# Sheet1.net
KiCad netlist of a schematic drawn in Altium Designer
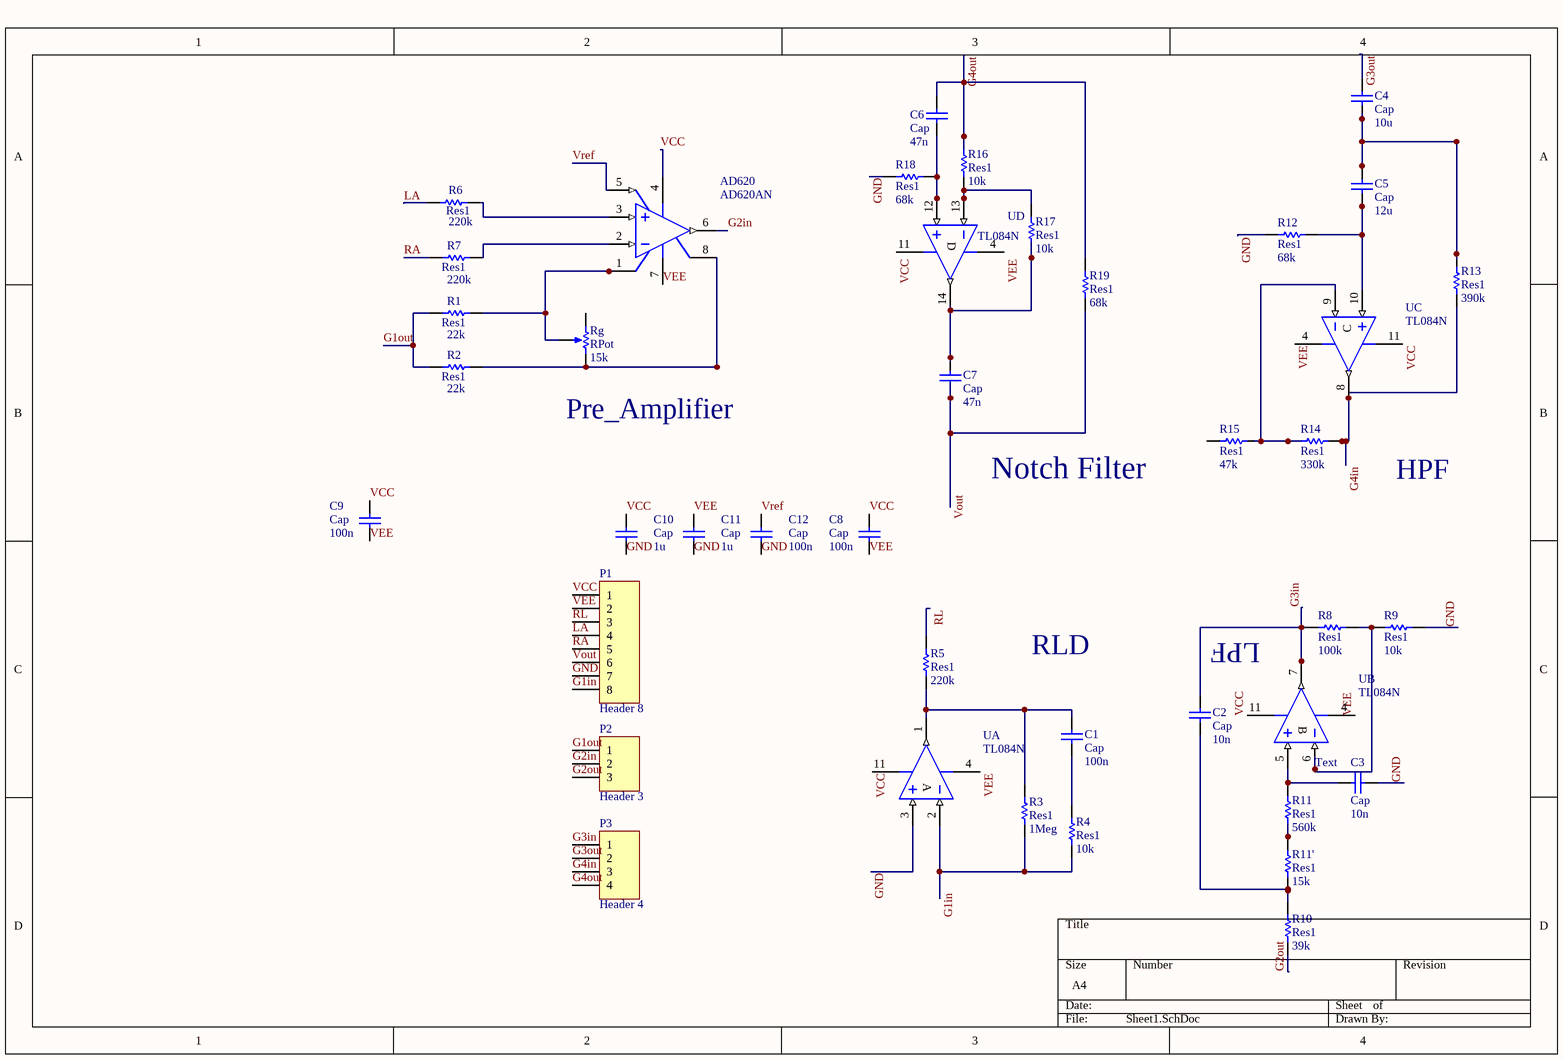
[diagram p0: Sheet1.SchDoc]

(export (version "E")
  (design (tool "Eeschema 10.0.6"))
  (components
    (comp (ref "AD620")
      (value "AD620AN")
      (footprint "N-8")
      (description "Low-Cost, Low-Power Instrumentation Amplifier")
      (fields (field (name "PUBLISHER") "Altium Limited"))
      (libsource (lib "AD Instrumentation Amplifier") (part "AD620AN"))
    )
    (comp (ref "C1")
      (value "Cap")
      (footprint "RAD-0.3")
      (description "Capacitor")
      (fields (field (name "ALTIUM_VALUE") "100n") (field (name "PUBLISHER") "Altium Limited"))
      (libsource (lib "Miscellaneous Devices") (part "Cap"))
    )
    (comp (ref "C2")
      (value "Cap")
      (footprint "RAD-0.3")
      (description "Capacitor")
      (fields (field (name "ALTIUM_VALUE") "10n") (field (name "PUBLISHER") "Altium Limited"))
      (libsource (lib "Miscellaneous Devices") (part "Cap"))
    )
    (comp (ref "C3")
      (value "Cap")
      (footprint "RAD-0.3")
      (description "Capacitor")
      (fields (field (name "ALTIUM_VALUE") "10n") (field (name "PUBLISHER") "Altium Limited"))
      (libsource (lib "Miscellaneous Devices") (part "Cap"))
    )
    (comp (ref "C4")
      (value "Cap")
      (footprint "RAD-0.3")
      (description "Capacitor")
      (fields (field (name "ALTIUM_VALUE") "10u") (field (name "PUBLISHER") "Altium Limited"))
      (libsource (lib "Miscellaneous Devices") (part "Cap"))
    )
    (comp (ref "C5")
      (value "Cap")
      (footprint "RAD-0.3")
      (description "Capacitor")
      (fields (field (name "ALTIUM_VALUE") "12u") (field (name "PUBLISHER") "Altium Limited"))
      (libsource (lib "Miscellaneous Devices") (part "Cap"))
    )
    (comp (ref "C6")
      (value "Cap")
      (footprint "RAD-0.3")
      (description "Capacitor")
      (fields (field (name "ALTIUM_VALUE") "47n") (field (name "PUBLISHER") "Altium Limited"))
      (libsource (lib "Miscellaneous Devices") (part "Cap"))
    )
    (comp (ref "C7")
      (value "Cap")
      (footprint "RAD-0.3")
      (description "Capacitor")
      (fields (field (name "ALTIUM_VALUE") "47n") (field (name "PUBLISHER") "Altium Limited"))
      (libsource (lib "Miscellaneous Devices") (part "Cap"))
    )
    (comp (ref "C8")
      (value "Cap")
      (footprint "RAD-0.3")
      (description "Capacitor")
      (fields (field (name "ALTIUM_VALUE") "100n") (field (name "PUBLISHER") "Altium Limited"))
      (libsource (lib "Miscellaneous Devices") (part "Cap"))
    )
    (comp (ref "C9")
      (value "Cap")
      (footprint "RAD-0.3")
      (description "Capacitor")
      (fields (field (name "ALTIUM_VALUE") "100n") (field (name "PUBLISHER") "Altium Limited"))
      (libsource (lib "Miscellaneous Devices") (part "Cap"))
    )
    (comp (ref "C10")
      (value "Cap")
      (footprint "RAD-0.3")
      (description "Capacitor")
      (fields (field (name "ALTIUM_VALUE") "1u") (field (name "PUBLISHER") "Altium Limited"))
      (libsource (lib "Miscellaneous Devices") (part "Cap"))
    )
    (comp (ref "C11")
      (value "Cap")
      (footprint "RAD-0.3")
      (description "Capacitor")
      (fields (field (name "ALTIUM_VALUE") "1u") (field (name "PUBLISHER") "Altium Limited"))
      (libsource (lib "Miscellaneous Devices") (part "Cap"))
    )
    (comp (ref "C12")
      (value "Cap")
      (footprint "RAD-0.3")
      (description "Capacitor")
      (fields (field (name "ALTIUM_VALUE") "100n") (field (name "PUBLISHER") "Altium Limited"))
      (libsource (lib "Miscellaneous Devices") (part "Cap"))
    )
    (comp (ref "P1")
      (value "Header 8")
      (footprint "HDR1X8")
      (description "Header, 8-Pin")
      (fields (field (name "PUBLISHER") "Altium Limited"))
      (libsource (lib "Miscellaneous Connectors") (part "Header 8"))
    )
    (comp (ref "P2")
      (value "Header 3")
      (footprint "HDR1X3")
      (description "Header, 3-Pin")
      (fields (field (name "PUBLISHER") "Altium Limited"))
      (libsource (lib "Miscellaneous Connectors") (part "Header 3"))
    )
    (comp (ref "P3")
      (value "Header 4")
      (footprint "HDR1X4")
      (description "Header, 4-Pin")
      (fields (field (name "PUBLISHER") "Altium Limited"))
      (libsource (lib "Miscellaneous Connectors") (part "Header 4"))
    )
    (comp (ref "R1")
      (value "Res1")
      (footprint "AXIAL-0.3")
      (description "Resistor")
      (fields (field (name "ALTIUM_VALUE") "22k") (field (name "PUBLISHER") "Altium Limited"))
      (libsource (lib "Miscellaneous Devices") (part "Res1"))
    )
    (comp (ref "R2")
      (value "Res1")
      (footprint "AXIAL-0.3")
      (description "Resistor")
      (fields (field (name "ALTIUM_VALUE") "22k") (field (name "PUBLISHER") "Altium Limited"))
      (libsource (lib "Miscellaneous Devices") (part "Res1"))
    )
    (comp (ref "R3")
      (value "Res1")
      (footprint "AXIAL-0.3")
      (description "Resistor")
      (fields (field (name "ALTIUM_VALUE") "1Meg") (field (name "PUBLISHER") "Altium Limited"))
      (libsource (lib "Miscellaneous Devices") (part "Res1"))
    )
    (comp (ref "R4")
      (value "Res1")
      (footprint "AXIAL-0.3")
      (description "Resistor")
      (fields (field (name "ALTIUM_VALUE") "10k") (field (name "PUBLISHER") "Altium Limited"))
      (libsource (lib "Miscellaneous Devices") (part "Res1"))
    )
    (comp (ref "R5")
      (value "Res1")
      (footprint "AXIAL-0.3")
      (description "Resistor")
      (fields (field (name "ALTIUM_VALUE") "220k") (field (name "PUBLISHER") "Altium Limited"))
      (libsource (lib "Miscellaneous Devices") (part "Res1"))
    )
    (comp (ref "R6")
      (value "Res1")
      (footprint "AXIAL-0.3")
      (description "Resistor")
      (fields (field (name "ALTIUM_VALUE") "220k") (field (name "PUBLISHER") "Altium Limited"))
      (libsource (lib "Miscellaneous Devices") (part "Res1"))
    )
    (comp (ref "R7")
      (value "Res1")
      (footprint "AXIAL-0.3")
      (description "Resistor")
      (fields (field (name "ALTIUM_VALUE") "220k") (field (name "PUBLISHER") "Altium Limited"))
      (libsource (lib "Miscellaneous Devices") (part "Res1"))
    )
    (comp (ref "R8")
      (value "Res1")
      (footprint "AXIAL-0.3")
      (description "Resistor")
      (fields (field (name "ALTIUM_VALUE") "100k") (field (name "PUBLISHER") "Altium Limited"))
      (libsource (lib "Miscellaneous Devices") (part "Res1"))
    )
    (comp (ref "R9")
      (value "Res1")
      (footprint "AXIAL-0.3")
      (description "Resistor")
      (fields (field (name "ALTIUM_VALUE") "10k") (field (name "PUBLISHER") "Altium Limited"))
      (libsource (lib "Miscellaneous Devices") (part "Res1"))
    )
    (comp (ref "R10")
      (value "Res1")
      (footprint "AXIAL-0.3")
      (description "Resistor")
      (fields (field (name "ALTIUM_VALUE") "39k") (field (name "PUBLISHER") "Altium Limited"))
      (libsource (lib "Miscellaneous Devices") (part "Res1"))
    )
    (comp (ref "R11")
      (value "Res1")
      (footprint "AXIAL-0.3")
      (description "Resistor")
      (fields (field (name "ALTIUM_VALUE") "560k") (field (name "PUBLISHER") "Altium Limited"))
      (libsource (lib "Miscellaneous Devices") (part "Res1"))
    )
    (comp (ref "R11'")
      (value "Res1")
      (footprint "AXIAL-0.3")
      (description "Resistor")
      (fields (field (name "ALTIUM_VALUE") "15k") (field (name "PUBLISHER") "Altium Limited"))
      (libsource (lib "Miscellaneous Devices") (part "Res1"))
    )
    (comp (ref "R12")
      (value "Res1")
      (footprint "AXIAL-0.3")
      (description "Resistor")
      (fields (field (name "ALTIUM_VALUE") "68k") (field (name "PUBLISHER") "Altium Limited"))
      (libsource (lib "Miscellaneous Devices") (part "Res1"))
    )
    (comp (ref "R13")
      (value "Res1")
      (footprint "AXIAL-0.3")
      (description "Resistor")
      (fields (field (name "ALTIUM_VALUE") "390k") (field (name "PUBLISHER") "Altium Limited"))
      (libsource (lib "Miscellaneous Devices") (part "Res1"))
    )
    (comp (ref "R14")
      (value "Res1")
      (footprint "AXIAL-0.3")
      (description "Resistor")
      (fields (field (name "ALTIUM_VALUE") "330k") (field (name "PUBLISHER") "Altium Limited"))
      (libsource (lib "Miscellaneous Devices") (part "Res1"))
    )
    (comp (ref "R15")
      (value "Res1")
      (footprint "AXIAL-0.3")
      (description "Resistor")
      (fields (field (name "ALTIUM_VALUE") "47k") (field (name "PUBLISHER") "Altium Limited"))
      (libsource (lib "Miscellaneous Devices") (part "Res1"))
    )
    (comp (ref "R16")
      (value "Res1")
      (footprint "AXIAL-0.3")
      (description "Resistor")
      (fields (field (name "ALTIUM_VALUE") "10k") (field (name "PUBLISHER") "Altium Limited"))
      (libsource (lib "Miscellaneous Devices") (part "Res1"))
    )
    (comp (ref "R17")
      (value "Res1")
      (footprint "AXIAL-0.3")
      (description "Resistor")
      (fields (field (name "ALTIUM_VALUE") "10k") (field (name "PUBLISHER") "Altium Limited"))
      (libsource (lib "Miscellaneous Devices") (part "Res1"))
    )
    (comp (ref "R18")
      (value "Res1")
      (footprint "AXIAL-0.3")
      (description "Resistor")
      (fields (field (name "ALTIUM_VALUE") "68k") (field (name "PUBLISHER") "Altium Limited"))
      (libsource (lib "Miscellaneous Devices") (part "Res1"))
    )
    (comp (ref "R19")
      (value "Res1")
      (footprint "AXIAL-0.3")
      (description "Resistor")
      (fields (field (name "ALTIUM_VALUE") "68k") (field (name "PUBLISHER") "Altium Limited"))
      (libsource (lib "Miscellaneous Devices") (part "Res1"))
    )
    (comp (ref "Rg")
      (value "RPot")
      (footprint "VR5")
      (description "Potentiometer")
      (fields (field (name "ALTIUM_VALUE") "15k") (field (name "PUBLISHER") "Altium Limited"))
      (libsource (lib "Miscellaneous Devices") (part "RPot"))
    )
    (comp (ref "U")
      (value "TL084N")
      (footprint "N014")
      (description "JFET-Input Operational Amplifier")
      (fields (field (name "PUBLISHER") "Altium Limited"))
      (libsource (lib "TI Operational Amplifier") (part "TL084N"))
    )
  )
  (nets
    (net (code "2") (name "/G1in") (class "Default")
      (node (ref "P1") (pin "8") (pinfunction "8_8") (pintype "passive"))
      (node (ref "R3") (pin "2") (pinfunction "2_2") (pintype "passive"))
      (node (ref "R4") (pin "2") (pinfunction "2_2") (pintype "passive"))
      (node (ref "U") (pin "2") (pinfunction "IN-_2") (pintype "input"))
    )
    (net (code "3") (name "/G1out") (class "Default")
      (node (ref "P2") (pin "1") (pinfunction "1_1") (pintype "passive"))
      (node (ref "R1") (pin "1") (pinfunction "1_1") (pintype "passive"))
      (node (ref "R2") (pin "1") (pinfunction "1_1") (pintype "passive"))
    )
    (net (code "4") (name "/G2in") (class "Default")
      (node (ref "AD620") (pin "6") (pinfunction "OUT_6") (pintype "output"))
      (node (ref "P2") (pin "2") (pinfunction "2_2") (pintype "passive"))
    )
    (net (code "5") (name "/G2out") (class "Default")
      (node (ref "P2") (pin "3") (pinfunction "3_3") (pintype "passive"))
      (node (ref "R10") (pin "1") (pinfunction "1_1") (pintype "passive"))
    )
    (net (code "6") (name "/G3in") (class "Default")
      (node (ref "C2") (pin "2") (pinfunction "2_2") (pintype "passive"))
      (node (ref "P3") (pin "1") (pinfunction "1_1") (pintype "passive"))
      (node (ref "U") (pin "7") (pinfunction "OUT_7") (pintype "output"))
    )
    (net (code "7") (name "/G3out") (class "Default")
      (node (ref "C4") (pin "1") (pinfunction "1_1") (pintype "passive"))
      (node (ref "P3") (pin "2") (pinfunction "2_2") (pintype "passive"))
    )
    (net (code "8") (name "/G4in") (class "Default")
      (node (ref "P3") (pin "3") (pinfunction "3_3") (pintype "passive"))
      (node (ref "R13") (pin "2") (pinfunction "2_2") (pintype "passive"))
      (node (ref "R14") (pin "2") (pinfunction "2_2") (pintype "passive"))
      (node (ref "U") (pin "8") (pinfunction "OUT_8") (pintype "output"))
    )
    (net (code "9") (name "/G4out") (class "Default")
      (node (ref "C6") (pin "1") (pinfunction "1_1") (pintype "passive"))
      (node (ref "P3") (pin "4") (pinfunction "4_4") (pintype "passive"))
      (node (ref "R16") (pin "1") (pinfunction "1_1") (pintype "passive"))
      (node (ref "R19") (pin "1") (pinfunction "1_1") (pintype "passive"))
    )
    (net (code "10") (name "/GND") (class "Default")
      (node (ref "C10") (pin "2") (pinfunction "2_2") (pintype "passive"))
      (node (ref "C11") (pin "2") (pinfunction "2_2") (pintype "passive"))
      (node (ref "C12") (pin "2") (pinfunction "2_2") (pintype "passive"))
      (node (ref "C3") (pin "1") (pinfunction "1_1") (pintype "passive"))
      (node (ref "P1") (pin "7") (pinfunction "7_7") (pintype "passive"))
      (node (ref "R12") (pin "1") (pinfunction "1_1") (pintype "passive"))
      (node (ref "R18") (pin "1") (pinfunction "1_1") (pintype "passive"))
      (node (ref "R9") (pin "1") (pinfunction "1_1") (pintype "passive"))
      (node (ref "U") (pin "3") (pinfunction "IN+_3") (pintype "input"))
    )
    (net (code "11") (name "/LA") (class "Default")
      (node (ref "P1") (pin "4") (pinfunction "4_4") (pintype "passive"))
      (node (ref "R6") (pin "1") (pinfunction "1_1") (pintype "passive"))
    )
    (net (code "12") (name "/RA") (class "Default")
      (node (ref "P1") (pin "5") (pinfunction "5_5") (pintype "passive"))
      (node (ref "R7") (pin "1") (pinfunction "1_1") (pintype "passive"))
    )
    (net (code "13") (name "/RL") (class "Default")
      (node (ref "P1") (pin "3") (pinfunction "3_3") (pintype "passive"))
      (node (ref "R5") (pin "1") (pinfunction "1_1") (pintype "passive"))
    )
    (net (code "14") (name "/VCC") (class "Default")
      (node (ref "AD620") (pin "4") (pinfunction "V-_4") (pintype "power_in"))
      (node (ref "C10") (pin "1") (pinfunction "1_1") (pintype "passive"))
      (node (ref "C8") (pin "1") (pinfunction "1_1") (pintype "passive"))
      (node (ref "C9") (pin "1") (pinfunction "1_1") (pintype "passive"))
      (node (ref "P1") (pin "1") (pinfunction "1_1") (pintype "passive"))
      (node (ref "U") (pin "11") (pinfunction "V-_11") (pintype "power_in"))
    )
    (net (code "15") (name "/VEE") (class "Default")
      (node (ref "AD620") (pin "7") (pinfunction "V+_7") (pintype "power_in"))
      (node (ref "C11") (pin "1") (pinfunction "1_1") (pintype "passive"))
      (node (ref "C8") (pin "2") (pinfunction "2_2") (pintype "passive"))
      (node (ref "C9") (pin "2") (pinfunction "2_2") (pintype "passive"))
      (node (ref "P1") (pin "2") (pinfunction "2_2") (pintype "passive"))
      (node (ref "U") (pin "4") (pinfunction "V+_4") (pintype "power_in"))
    )
    (net (code "16") (name "/Vout") (class "Default")
      (node (ref "C7") (pin "2") (pinfunction "2_2") (pintype "passive"))
      (node (ref "P1") (pin "6") (pinfunction "6_6") (pintype "passive"))
      (node (ref "R19") (pin "2") (pinfunction "2_2") (pintype "passive"))
    )
    (net (code "17") (name "/Vref") (class "Default")
      (node (ref "AD620") (pin "5") (pinfunction "REF_5") (pintype "input"))
      (node (ref "C12") (pin "1") (pinfunction "1_1") (pintype "passive"))
    )
    (net (code "18") (name "Net-(AD620-+IN)") (class "Default")
      (node (ref "AD620") (pin "3") (pinfunction "+IN_3") (pintype "input"))
      (node (ref "R6") (pin "2") (pinfunction "2_2") (pintype "passive"))
    )
    (net (code "19") (name "Net-(AD620--IN)") (class "Default")
      (node (ref "AD620") (pin "2") (pinfunction "-IN_2") (pintype "input"))
      (node (ref "R7") (pin "2") (pinfunction "2_2") (pintype "passive"))
    )
    (net (code "20") (name "Net-(C1-Pad2)") (class "Default")
      (node (ref "C1") (pin "2") (pinfunction "2_2") (pintype "passive"))
      (node (ref "R4") (pin "1") (pinfunction "1_1") (pintype "passive"))
    )
    (net (code "21") (name "Net-(C2-Pad1)") (class "Default")
      (node (ref "C2") (pin "1") (pinfunction "1_1") (pintype "passive"))
      (node (ref "R10") (pin "2") (pinfunction "2_2") (pintype "passive"))
      (node (ref "R11'") (pin "1") (pinfunction "1_1") (pintype "passive"))
    )
    (net (code "22") (name "Net-(C4-Pad2)") (class "Default")
      (node (ref "C4") (pin "2") (pinfunction "2_2") (pintype "passive"))
      (node (ref "C5") (pin "1") (pinfunction "1_1") (pintype "passive"))
      (node (ref "R13") (pin "1") (pinfunction "1_1") (pintype "passive"))
    )
    (net (code "23") (name "Net-(R11'-Pad2)") (class "Default")
      (node (ref "R11") (pin "1") (pinfunction "1_1") (pintype "passive"))
      (node (ref "R11'") (pin "2") (pinfunction "2_2") (pintype "passive"))
    )
    (net (code "24") (name "Net-(Rg-BOT)") (class "Default")
      (node (ref "AD620") (pin "8") (pinfunction "RG_8") (pintype "passive"))
      (node (ref "R2") (pin "2") (pinfunction "2_2") (pintype "passive"))
      (node (ref "Rg") (pin "2") (pinfunction "BOT_2") (pintype "passive"))
    )
    (net (code "25") (name "Net-(Rg-TAP)") (class "Default")
      (node (ref "AD620") (pin "1") (pinfunction "RG_1") (pintype "passive"))
      (node (ref "R1") (pin "2") (pinfunction "2_2") (pintype "passive"))
      (node (ref "Rg") (pin "3") (pinfunction "TAP_3") (pintype "passive"))
    )
    (net (code "26") (name "Net-(UA-OUT)") (class "Default")
      (node (ref "C1") (pin "1") (pinfunction "1_1") (pintype "passive"))
      (node (ref "R3") (pin "1") (pinfunction "1_1") (pintype "passive"))
      (node (ref "R5") (pin "2") (pinfunction "2_2") (pintype "passive"))
      (node (ref "U") (pin "1") (pinfunction "OUT_1") (pintype "output"))
    )
    (net (code "27") (name "Net-(UB-IN+)") (class "Default")
      (node (ref "C3") (pin "2") (pinfunction "2_2") (pintype "passive"))
      (node (ref "R11") (pin "2") (pinfunction "2_2") (pintype "passive"))
      (node (ref "U") (pin "5") (pinfunction "IN+_5") (pintype "input"))
    )
    (net (code "28") (name "Net-(UB-IN-)") (class "Default")
      (node (ref "R8") (pin "1") (pinfunction "1_1") (pintype "passive"))
      (node (ref "R9") (pin "2") (pinfunction "2_2") (pintype "passive"))
      (node (ref "U") (pin "6") (pinfunction "IN-_6") (pintype "input"))
    )
    (net (code "29") (name "Net-(UC-IN+)") (class "Default")
      (node (ref "C5") (pin "2") (pinfunction "2_2") (pintype "passive"))
      (node (ref "R12") (pin "2") (pinfunction "2_2") (pintype "passive"))
      (node (ref "U") (pin "10") (pinfunction "IN+_10") (pintype "input"))
    )
    (net (code "30") (name "Net-(UC-IN-)") (class "Default")
      (node (ref "R14") (pin "1") (pinfunction "1_1") (pintype "passive"))
      (node (ref "R15") (pin "2") (pinfunction "2_2") (pintype "passive"))
      (node (ref "U") (pin "9") (pinfunction "IN-_9") (pintype "input"))
    )
    (net (code "31") (name "Net-(UD-IN+)") (class "Default")
      (node (ref "C6") (pin "2") (pinfunction "2_2") (pintype "passive"))
      (node (ref "R18") (pin "2") (pinfunction "2_2") (pintype "passive"))
      (node (ref "U") (pin "12") (pinfunction "IN+_12") (pintype "input"))
    )
    (net (code "32") (name "Net-(UD-IN-)") (class "Default")
      (node (ref "R16") (pin "2") (pinfunction "2_2") (pintype "passive"))
      (node (ref "R17") (pin "1") (pinfunction "1_1") (pintype "passive"))
      (node (ref "U") (pin "13") (pinfunction "IN-_13") (pintype "input"))
    )
    (net (code "33") (name "Net-(UD-OUT)") (class "Default")
      (node (ref "C7") (pin "1") (pinfunction "1_1") (pintype "passive"))
      (node (ref "R17") (pin "2") (pinfunction "2_2") (pintype "passive"))
      (node (ref "U") (pin "14") (pinfunction "OUT_14") (pintype "output"))
    )
    (net (code "34") (name "unconnected-(R8-Pad2)") (class "Default")
      (node (ref "R8") (pin "2") (pinfunction "2_2") (pintype "passive"))
    )
    (net (code "35") (name "unconnected-(R15-Pad1)") (class "Default")
      (node (ref "R15") (pin "1") (pinfunction "1_1") (pintype "passive"))
    )
    (net (code "36") (name "unconnected-(Rg-TOP-Pad1)") (class "Default")
      (node (ref "Rg") (pin "1") (pinfunction "TOP_1") (pintype "passive"))
    )
    (net (code "37") (name "unconnected-(UB-V+-Pad4)") (class "Default")
      (node (ref "U") (pin "4") (pinfunction "V+_4") (pintype "power_in"))
    )
    (net (code "38") (name "unconnected-(UB-V--Pad11)") (class "Default")
      (node (ref "U") (pin "11") (pinfunction "V-_11") (pintype "power_in"))
    )
    (net (code "39") (name "unconnected-(UD-V+-Pad4)") (class "Default")
      (node (ref "U") (pin "4") (pinfunction "V+_4") (pintype "power_in"))
    )
    (net (code "40") (name "unconnected-(UD-V--Pad11)") (class "Default")
      (node (ref "U") (pin "11") (pinfunction "V-_11") (pintype "power_in"))
    )
  )
)
